# Ant_V1_Sheet.net
KiCad netlist of a schematic drawn in Altium Designer
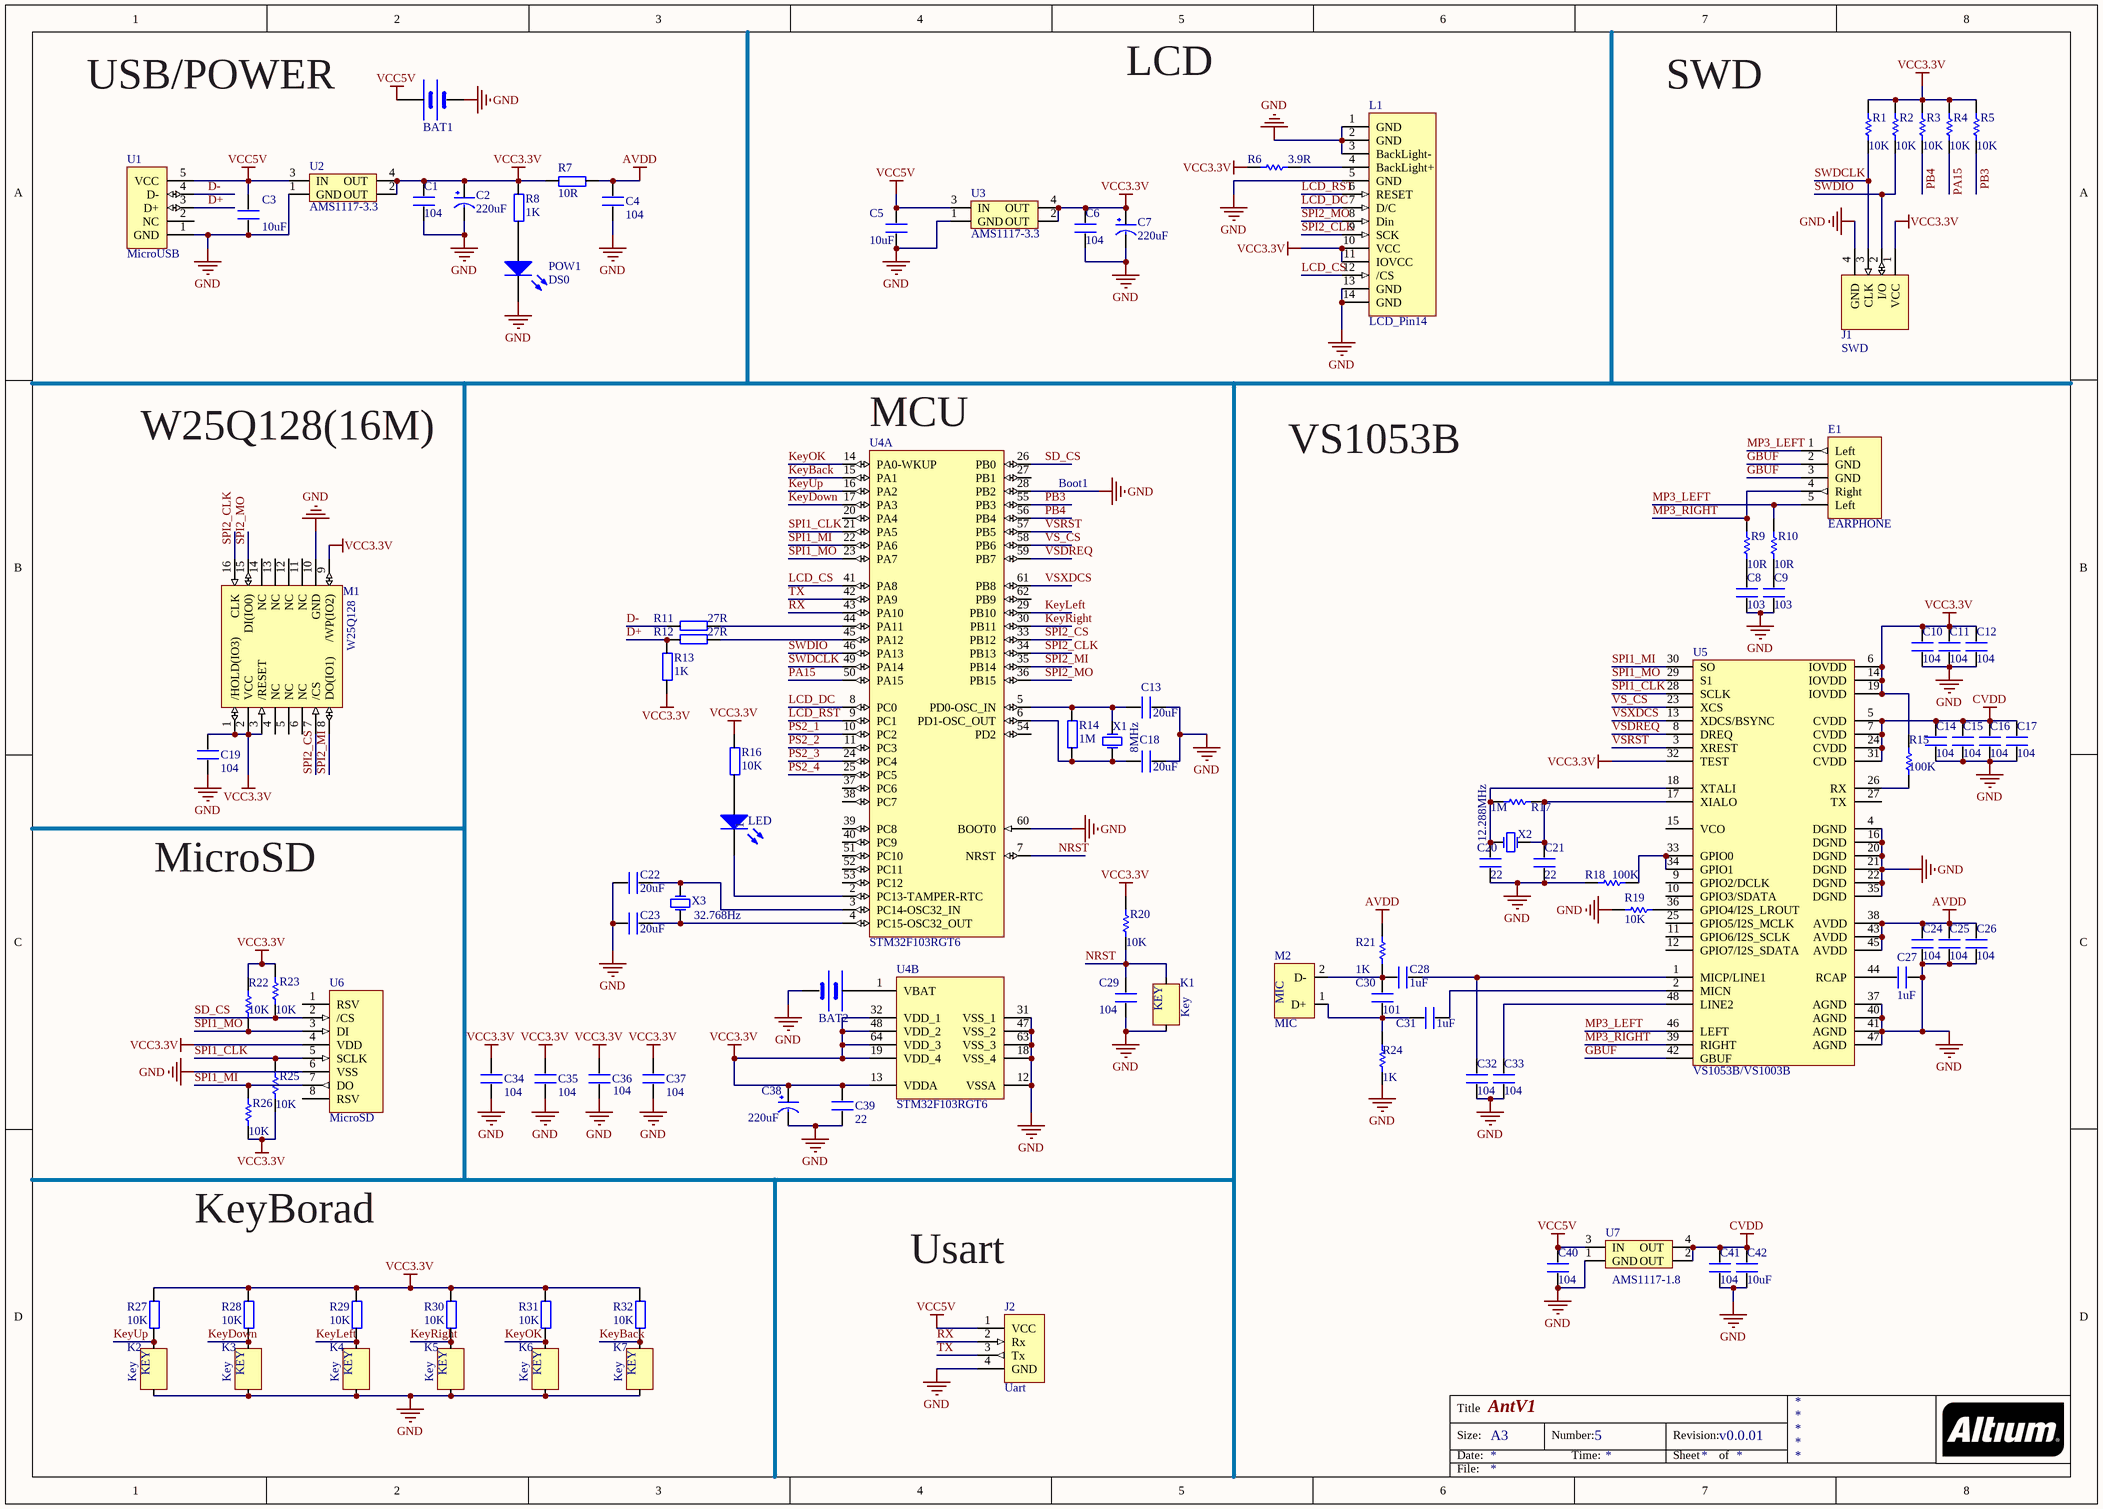
[diagram p0: Ant_V1_Sheet.SchDoc]

(export (version "E")
  (design (tool "Eeschema 10.0.6"))
  (components
    (comp (ref "1")
      (value "LED")
      (footprint "LED_LITTLE")
      (description "Typical RED, GREEN, YELLOW, AMBER GaAs LED")
      (fields (field (name "PUBLISHER") "Altium Limited"))
      (libsource (lib "MP3模块封装库") (part "LED2"))
    )
    (comp (ref "BAT1") (value "BATT") (footprint "BATTERY") (libsource (lib "EliteSTM32封装库") (part "BAT")))
    (comp (ref "BAT2") (value "BATT") (footprint "BATTERY") (libsource (lib "EliteSTM32封装库") (part "BAT")))
    (comp (ref "C1") (value "104") (footprint "0805") (libsource (lib "MP3模块封装库") (part "C")))
    (comp (ref "C2") (value "220uF") (footprint "0805") (libsource (lib "MP3模块封装库") (part "CAP")))
    (comp (ref "C3") (value "10uF") (footprint "0805") (libsource (lib "EliteSTM32封装库") (part "C_2")))
    (comp (ref "C4") (value "104") (footprint "0805") (libsource (lib "MP3模块封装库") (part "C")))
    (comp (ref "C5") (value "10uF") (footprint "0805") (libsource (lib "EliteSTM32封装库") (part "C_2")))
    (comp (ref "C6") (value "104") (footprint "0805") (libsource (lib "MP3模块封装库") (part "C")))
    (comp (ref "C7") (value "220uF") (footprint "0805") (libsource (lib "MP3模块封装库") (part "CAP")))
    (comp (ref "C8") (value "103") (footprint "0805") (libsource (lib "MP3模块封装库") (part "C")))
    (comp (ref "C9") (value "103") (footprint "0805") (libsource (lib "MP3模块封装库") (part "C")))
    (comp (ref "C10") (value "104") (footprint "0805") (libsource (lib "MP3模块封装库") (part "C")))
    (comp (ref "C11") (value "104") (footprint "0805") (libsource (lib "MP3模块封装库") (part "C")))
    (comp (ref "C12") (value "104") (footprint "0805") (libsource (lib "MP3模块封装库") (part "C")))
    (comp (ref "C13") (value "20uF") (footprint "0805") (libsource (lib "EliteSTM32封装库") (part "C_2")))
    (comp (ref "C14") (value "104") (footprint "0805") (libsource (lib "MP3模块封装库") (part "C")))
    (comp (ref "C15") (value "104") (footprint "0805") (libsource (lib "MP3模块封装库") (part "C")))
    (comp (ref "C16") (value "104") (footprint "0805") (libsource (lib "MP3模块封装库") (part "C")))
    (comp (ref "C17") (value "104") (footprint "0805") (libsource (lib "MP3模块封装库") (part "C")))
    (comp (ref "C18") (value "20uF") (footprint "0805") (libsource (lib "EliteSTM32封装库") (part "C_2")))
    (comp (ref "C19") (value "104") (footprint "0805") (libsource (lib "EliteSTM32封装库") (part "C_2")))
    (comp (ref "C20") (value "22") (footprint "0805") (libsource (lib "MP3模块封装库") (part "C")))
    (comp (ref "C21") (value "22") (footprint "0805") (libsource (lib "MP3模块封装库") (part "C")))
    (comp (ref "C22") (value "20uF") (footprint "0805") (libsource (lib "EliteSTM32封装库") (part "C_2")))
    (comp (ref "C23") (value "20uF") (footprint "0805") (libsource (lib "EliteSTM32封装库") (part "C_2")))
    (comp (ref "C24") (value "104") (footprint "0805") (libsource (lib "MP3模块封装库") (part "C")))
    (comp (ref "C25") (value "104") (footprint "0805") (libsource (lib "MP3模块封装库") (part "C")))
    (comp (ref "C26") (value "104") (footprint "0805") (libsource (lib "MP3模块封装库") (part "C")))
    (comp (ref "C27") (value "1uF") (footprint "0805") (libsource (lib "MP3模块封装库") (part "C")))
    (comp (ref "C28") (value "1uF") (footprint "0805") (libsource (lib "MP3模块封装库") (part "C")))
    (comp (ref "C29") (value "104") (footprint "0805") (libsource (lib "EliteSTM32封装库") (part "C")))
    (comp (ref "C30") (value "101") (footprint "0805") (libsource (lib "MP3模块封装库") (part "C")))
    (comp (ref "C31") (value "1uF") (footprint "0805") (libsource (lib "MP3模块封装库") (part "C")))
    (comp (ref "C32") (value "104") (footprint "0805") (libsource (lib "MP3模块封装库") (part "C")))
    (comp (ref "C33") (value "104") (footprint "0805") (libsource (lib "MP3模块封装库") (part "C")))
    (comp (ref "C34") (value "104") (footprint "0805") (libsource (lib "EliteSTM32封装库") (part "C_2")))
    (comp (ref "C35") (value "104") (footprint "0805") (libsource (lib "EliteSTM32封装库") (part "C_2")))
    (comp (ref "C36") (value "104") (footprint "0805") (libsource (lib "EliteSTM32封装库") (part "C_2")))
    (comp (ref "C37") (value "104") (footprint "0805") (libsource (lib "EliteSTM32封装库") (part "C_2")))
    (comp (ref "C38") (value "220uF") (footprint "0805") (libsource (lib "MP3模块封装库") (part "CAP")))
    (comp (ref "C39") (value "22") (footprint "0805") (libsource (lib "MP3模块封装库") (part "C")))
    (comp (ref "C40") (value "104") (footprint "0805") (libsource (lib "MP3模块封装库") (part "C")))
    (comp (ref "C41") (value "104") (footprint "0805") (libsource (lib "MP3模块封装库") (part "C")))
    (comp (ref "C42") (value "10uF") (footprint "0805") (libsource (lib "MP3模块封装库") (part "C")))
    (comp (ref "E1")
      (value "EARPHONE")
      (footprint "EARPHONE")
      (libsource (lib "Ant_V1_Schlib") (part "EARPHONE"))
    )
    (comp (ref "J1") (value "SWD") (footprint "SWD") (libsource (lib "Ant_V1_Schlib") (part "SWD")))
    (comp (ref "J2") (value "Uart") (footprint "Uart") (libsource (lib "Ant_V1_Schlib") (part "Uart")))
    (comp (ref "K1") (value "Key") (footprint "KEY") (libsource (lib "Ant_V1_Schlib") (part "Key")))
    (comp (ref "K2") (value "Key") (footprint "KEY") (libsource (lib "Ant_V1_Schlib") (part "Key")))
    (comp (ref "K3") (value "Key") (footprint "KEY") (libsource (lib "Ant_V1_Schlib") (part "Key")))
    (comp (ref "K4") (value "Key") (footprint "KEY") (libsource (lib "Ant_V1_Schlib") (part "Key")))
    (comp (ref "K5") (value "Key") (footprint "KEY") (libsource (lib "Ant_V1_Schlib") (part "Key")))
    (comp (ref "K6") (value "Key") (footprint "KEY") (libsource (lib "Ant_V1_Schlib") (part "Key")))
    (comp (ref "K7") (value "Key") (footprint "KEY") (libsource (lib "Ant_V1_Schlib") (part "Key")))
    (comp (ref "L1")
      (value "LCD_Pin14")
      (footprint "LCD_PIN14_Rctify")
      (libsource (lib "Ant_V1_Schlib") (part "LCD_Pin14"))
    )
    (comp (ref "M1")
      (value "W25Q128")
      (footprint "W25Q128")
      (libsource (lib "Ant_V1_Schlib") (part "W25Q128"))
    )
    (comp (ref "M2") (value "MIC") (footprint "MIC") (libsource (lib "Ant_V1_Schlib") (part "MIC")))
    (comp (ref "POW1")
      (value "DS0")
      (footprint "LED_LITTLE")
      (description "Typical RED, GREEN, YELLOW, AMBER GaAs LED")
      (fields (field (name "PUBLISHER") "Altium Limited"))
      (libsource (lib "MP3模块封装库") (part "LED2"))
    )
    (comp (ref "R1")
      (value "10K")
      (footprint "0805")
      (description "Resistor")
      (fields (field (name "PUBLISHER") "Altium Limited"))
      (libsource (lib "Miscellaneous Devices") (part "Res1"))
    )
    (comp (ref "R2")
      (value "10K")
      (footprint "0805")
      (description "Resistor")
      (fields (field (name "PUBLISHER") "Altium Limited"))
      (libsource (lib "Miscellaneous Devices") (part "Res1"))
    )
    (comp (ref "R3")
      (value "10K")
      (footprint "0805")
      (description "Resistor")
      (fields (field (name "PUBLISHER") "Altium Limited"))
      (libsource (lib "Miscellaneous Devices") (part "Res1"))
    )
    (comp (ref "R4")
      (value "10K")
      (footprint "0805")
      (description "Resistor")
      (fields (field (name "PUBLISHER") "Altium Limited"))
      (libsource (lib "Miscellaneous Devices") (part "Res1"))
    )
    (comp (ref "R5")
      (value "10K")
      (footprint "0805")
      (description "Resistor")
      (fields (field (name "PUBLISHER") "Altium Limited"))
      (libsource (lib "Miscellaneous Devices") (part "Res1"))
    )
    (comp (ref "R6")
      (value "3.9R")
      (footprint "0805")
      (description "Resistor")
      (fields (field (name "PUBLISHER") "Altium Limited"))
      (libsource (lib "Miscellaneous Devices") (part "Res1"))
    )
    (comp (ref "R7") (value "10R") (footprint "0805") (libsource (lib "MP3模块封装库") (part "R")))
    (comp (ref "R8") (value "1K") (footprint "0805") (libsource (lib "MP3模块封装库") (part "R")))
    (comp (ref "R9")
      (value "10R")
      (footprint "0805")
      (description "Resistor")
      (fields (field (name "PUBLISHER") "Altium Limited"))
      (libsource (lib "Miscellaneous Devices") (part "Res1"))
    )
    (comp (ref "R10")
      (value "10R")
      (footprint "0805")
      (description "Resistor")
      (fields (field (name "PUBLISHER") "Altium Limited"))
      (libsource (lib "Miscellaneous Devices") (part "Res1"))
    )
    (comp (ref "R11") (value "27R") (footprint "0805") (libsource (lib "EliteSTM32封装库") (part "R")))
    (comp (ref "R12") (value "27R") (footprint "0805") (libsource (lib "EliteSTM32封装库") (part "R")))
    (comp (ref "R13") (value "1K") (footprint "0805") (libsource (lib "EliteSTM32封装库") (part "R")))
    (comp (ref "R14") (value "1M") (footprint "0805") (libsource (lib "EliteSTM32封装库") (part "R")))
    (comp (ref "R15")
      (value "100K")
      (footprint "0805")
      (description "Resistor")
      (fields (field (name "PUBLISHER") "Altium Limited"))
      (libsource (lib "Miscellaneous Devices") (part "Res1"))
    )
    (comp (ref "R16") (value "10K") (footprint "0805") (libsource (lib "EliteSTM32封装库") (part "R")))
    (comp (ref "R17")
      (value "1M")
      (footprint "0805")
      (description "Resistor")
      (fields (field (name "PUBLISHER") "Altium Limited"))
      (libsource (lib "Miscellaneous Devices") (part "Res1"))
    )
    (comp (ref "R18")
      (value "100K")
      (footprint "0805")
      (description "Resistor")
      (fields (field (name "PUBLISHER") "Altium Limited"))
      (libsource (lib "Miscellaneous Devices") (part "Res1"))
    )
    (comp (ref "R19")
      (value "10K")
      (footprint "0805")
      (description "Resistor")
      (fields (field (name "PUBLISHER") "Altium Limited"))
      (libsource (lib "Miscellaneous Devices") (part "Res1"))
    )
    (comp (ref "R20")
      (value "10K")
      (footprint "0805")
      (description "Resistor")
      (fields (field (name "PUBLISHER") "Altium Limited"))
      (libsource (lib "Miscellaneous Devices") (part "Res1"))
    )
    (comp (ref "R21")
      (value "1K")
      (footprint "0805")
      (description "Resistor")
      (fields (field (name "PUBLISHER") "Altium Limited"))
      (libsource (lib "Miscellaneous Devices") (part "Res1"))
    )
    (comp (ref "R22")
      (value "10K")
      (footprint "0805")
      (description "Resistor")
      (fields (field (name "PUBLISHER") "Altium Limited"))
      (libsource (lib "Miscellaneous Devices") (part "Res1"))
    )
    (comp (ref "R23")
      (value "10K")
      (footprint "0805")
      (description "Resistor")
      (fields (field (name "PUBLISHER") "Altium Limited"))
      (libsource (lib "Miscellaneous Devices") (part "Res1"))
    )
    (comp (ref "R24")
      (value "1K")
      (footprint "0805")
      (description "Resistor")
      (fields (field (name "PUBLISHER") "Altium Limited"))
      (libsource (lib "Miscellaneous Devices") (part "Res1"))
    )
    (comp (ref "R25")
      (value "10K")
      (footprint "0805")
      (description "Resistor")
      (fields (field (name "PUBLISHER") "Altium Limited"))
      (libsource (lib "Miscellaneous Devices") (part "Res1"))
    )
    (comp (ref "R26")
      (value "10K")
      (footprint "0805")
      (description "Resistor")
      (fields (field (name "PUBLISHER") "Altium Limited"))
      (libsource (lib "Miscellaneous Devices") (part "Res1"))
    )
    (comp (ref "R27") (value "10K") (footprint "0805") (libsource (lib "EliteSTM32封装库") (part "R")))
    (comp (ref "R28") (value "10K") (footprint "0805") (libsource (lib "EliteSTM32封装库") (part "R")))
    (comp (ref "R29") (value "10K") (footprint "0805") (libsource (lib "EliteSTM32封装库") (part "R")))
    (comp (ref "R30") (value "10K") (footprint "0805") (libsource (lib "EliteSTM32封装库") (part "R")))
    (comp (ref "R31") (value "10K") (footprint "0805") (libsource (lib "EliteSTM32封装库") (part "R")))
    (comp (ref "R32") (value "10K") (footprint "0805") (libsource (lib "EliteSTM32封装库") (part "R")))
    (comp (ref "U1") (value "MicroUSB") (footprint "USB") (libsource (lib "Ant_V1_Schlib") (part "MicroUSB")))
    (comp (ref "U2")
      (value "AMS1117-3.3")
      (footprint "AMS1117")
      (libsource (lib "MP3模块封装库") (part "AMS1117"))
    )
    (comp (ref "U3")
      (value "AMS1117-3.3")
      (footprint "AMS1117")
      (libsource (lib "MP3模块封装库") (part "AMS1117"))
    )
    (comp (ref "U4")
      (value "STM32F103RGT6")
      (footprint "STM-LQFP64_N")
      (libsource (lib "STMicroelectronics STM32 F1") (part "STM32F103RGT6"))
    )
    (comp (ref "U5")
      (value "VS1053B/VS1003B")
      (footprint "mTQFP48")
      (libsource (lib "MP3模块封装库") (part "VS1053"))
    )
    (comp (ref "U6")
      (value "MicroSD")
      (footprint "MICROSD")
      (libsource (lib "Ant_V1_Schlib") (part "MicroSD"))
    )
    (comp (ref "U7")
      (value "AMS1117-1.8")
      (footprint "AMS1117")
      (libsource (lib "MP3模块封装库") (part "AMS1117"))
    )
    (comp (ref "X1")
      (value "8MHz")
      (footprint "XTAL_8M")
      (description "Crystal Oscillator")
      (fields (field (name "PUBLISHER") "Altium Limited"))
      (libsource (lib "MP3模块封装库") (part "XTAL"))
    )
    (comp (ref "X2")
      (value "12.288MHz")
      (footprint "XTAL_12.288M")
      (description "Crystal Oscillator")
      (fields (field (name "PUBLISHER") "Altium Limited"))
      (libsource (lib "MP3模块封装库") (part "XTAL"))
    )
    (comp (ref "X3")
      (value "32.768Hz")
      (footprint "XTAL32.768K_4Pin'")
      (description "Crystal Oscillator")
      (fields (field (name "PUBLISHER") "Altium Limited"))
      (libsource (lib "MP3模块封装库") (part "XTAL"))
    )
  )
  (nets
    (net (code "1") (name "/D+") (class "Default")
      (node (ref "R12") (pin "2") (pintype "passive"))
      (node (ref "R13") (pin "2") (pintype "passive"))
      (node (ref "U1") (pin "3") (pinfunction "D+_3") (pintype "bidirectional"))
    )
    (net (code "2") (name "/D-") (class "Default")
      (node (ref "R11") (pin "2") (pintype "passive"))
      (node (ref "U1") (pin "4") (pinfunction "D-_4") (pintype "bidirectional"))
    )
    (net (code "3") (name "/GBUF") (class "Default")
      (node (ref "E1") (pin "2") (pinfunction "GND_2") (pintype "power_in"))
      (node (ref "E1") (pin "3") (pinfunction "GND_3") (pintype "power_in"))
      (node (ref "U5") (pin "42") (pinfunction "GBUF_42") (pintype "passive"))
    )
    (net (code "4") (name "/KeyBack") (class "Default")
      (node (ref "K7") (pin "1") (pinfunction "GND_1") (pintype "power_in"))
      (node (ref "R32") (pin "1") (pintype "passive"))
      (node (ref "U4") (pin "15") (pinfunction "PA1_15") (pintype "bidirectional"))
    )
    (net (code "5") (name "/KeyDown") (class "Default")
      (node (ref "K3") (pin "1") (pinfunction "GND_1") (pintype "power_in"))
      (node (ref "R28") (pin "1") (pintype "passive"))
      (node (ref "U4") (pin "17") (pinfunction "PA3_17") (pintype "bidirectional"))
    )
    (net (code "6") (name "/KeyLeft") (class "Default")
      (node (ref "K4") (pin "1") (pinfunction "GND_1") (pintype "power_in"))
      (node (ref "R29") (pin "1") (pintype "passive"))
      (node (ref "U4") (pin "29") (pinfunction "PB10_29") (pintype "bidirectional"))
    )
    (net (code "7") (name "/KeyOK") (class "Default")
      (node (ref "K6") (pin "1") (pinfunction "GND_1") (pintype "power_in"))
      (node (ref "R31") (pin "1") (pintype "passive"))
      (node (ref "U4") (pin "14") (pinfunction "PA0-WKUP_14") (pintype "bidirectional"))
    )
    (net (code "8") (name "/KeyRight") (class "Default")
      (node (ref "K5") (pin "1") (pinfunction "GND_1") (pintype "power_in"))
      (node (ref "R30") (pin "1") (pintype "passive"))
      (node (ref "U4") (pin "30") (pinfunction "PB11_30") (pintype "bidirectional"))
    )
    (net (code "9") (name "/KeyUp") (class "Default")
      (node (ref "K2") (pin "1") (pinfunction "GND_1") (pintype "power_in"))
      (node (ref "R27") (pin "1") (pintype "passive"))
      (node (ref "U4") (pin "16") (pinfunction "PA2_16") (pintype "bidirectional"))
    )
    (net (code "10") (name "/LCD_CS") (class "Default")
      (node (ref "L1") (pin "12") (pinfunction "/CS_12") (pintype "input"))
      (node (ref "U4") (pin "41") (pinfunction "PA8_41") (pintype "bidirectional"))
    )
    (net (code "11") (name "/LCD_DC") (class "Default")
      (node (ref "L1") (pin "7") (pinfunction "D/C_7") (pintype "input"))
      (node (ref "U4") (pin "8") (pinfunction "PC0_8") (pintype "bidirectional"))
    )
    (net (code "12") (name "/LCD_RST") (class "Default")
      (node (ref "L1") (pin "6") (pinfunction "RESET_6") (pintype "input"))
      (node (ref "U4") (pin "9") (pinfunction "PC1_9") (pintype "bidirectional"))
    )
    (net (code "13") (name "/MP3_LEFT") (class "Default")
      (node (ref "E1") (pin "1") (pinfunction "Left_1") (pintype "output"))
      (node (ref "E1") (pin "5") (pinfunction "Left_5") (pintype "tri_state"))
      (node (ref "R10") (pin "2") (pinfunction "2_2") (pintype "passive"))
      (node (ref "U5") (pin "46") (pinfunction "LEFT_46") (pintype "passive"))
    )
    (net (code "14") (name "/MP3_RIGHT") (class "Default")
      (node (ref "E1") (pin "4") (pinfunction "Right_4") (pintype "output"))
      (node (ref "R9") (pin "2") (pinfunction "2_2") (pintype "passive"))
      (node (ref "U5") (pin "39") (pinfunction "RIGHT_39") (pintype "passive"))
    )
    (net (code "15") (name "/NRST") (class "Default")
      (node (ref "C29") (pin "2") (pintype "passive"))
      (node (ref "K1") (pin "1") (pinfunction "GND_1") (pintype "power_in"))
      (node (ref "R20") (pin "1") (pinfunction "1_1") (pintype "passive"))
      (node (ref "U4") (pin "7") (pinfunction "NRST_7") (pintype "bidirectional"))
    )
    (net (code "16") (name "/PA15") (class "Default")
      (node (ref "R4") (pin "1") (pinfunction "1_1") (pintype "passive"))
      (node (ref "U4") (pin "50") (pinfunction "PA15_50") (pintype "bidirectional"))
    )
    (net (code "17") (name "/PB3") (class "Default")
      (node (ref "R5") (pin "1") (pinfunction "1_1") (pintype "passive"))
      (node (ref "U4") (pin "55") (pinfunction "PB3_55") (pintype "bidirectional"))
    )
    (net (code "18") (name "/PB4") (class "Default")
      (node (ref "R3") (pin "1") (pinfunction "1_1") (pintype "passive"))
      (node (ref "U4") (pin "56") (pinfunction "PB4_56") (pintype "bidirectional"))
    )
    (net (code "19") (name "/PS2_1") (class "Default")
      (node (ref "U4") (pin "10") (pinfunction "PC2_10") (pintype "bidirectional"))
    )
    (net (code "20") (name "/PS2_2") (class "Default")
      (node (ref "U4") (pin "11") (pinfunction "PC3_11") (pintype "bidirectional"))
    )
    (net (code "21") (name "/PS2_3") (class "Default")
      (node (ref "U4") (pin "24") (pinfunction "PC4_24") (pintype "bidirectional"))
    )
    (net (code "22") (name "/PS2_4") (class "Default")
      (node (ref "U4") (pin "25") (pinfunction "PC5_25") (pintype "bidirectional"))
    )
    (net (code "23") (name "/RX") (class "Default")
      (node (ref "J2") (pin "2") (pinfunction "Rx_2") (pintype "input"))
      (node (ref "U4") (pin "43") (pinfunction "PA10_43") (pintype "bidirectional"))
    )
    (net (code "24") (name "/SD_CS") (class "Default")
      (node (ref "R23") (pin "1") (pinfunction "1_1") (pintype "passive"))
      (node (ref "U4") (pin "26") (pinfunction "PB0_26") (pintype "bidirectional"))
      (node (ref "U6") (pin "2") (pinfunction "/CS_2") (pintype "input"))
    )
    (net (code "25") (name "/SPI1_CLK") (class "Default")
      (node (ref "R25") (pin "2") (pinfunction "2_2") (pintype "passive"))
      (node (ref "U4") (pin "21") (pinfunction "PA5_21") (pintype "bidirectional"))
      (node (ref "U5") (pin "28") (pinfunction "SCLK_28") (pintype "passive"))
      (node (ref "U6") (pin "5") (pinfunction "SCLK_5") (pintype "input"))
    )
    (net (code "26") (name "/SPI1_MI") (class "Default")
      (node (ref "R26") (pin "2") (pinfunction "2_2") (pintype "passive"))
      (node (ref "U4") (pin "22") (pinfunction "PA6_22") (pintype "bidirectional"))
      (node (ref "U5") (pin "30") (pinfunction "SO_30") (pintype "passive"))
      (node (ref "U6") (pin "7") (pinfunction "DO_7") (pintype "output"))
    )
    (net (code "27") (name "/SPI1_MO") (class "Default")
      (node (ref "R22") (pin "1") (pinfunction "1_1") (pintype "passive"))
      (node (ref "U4") (pin "23") (pinfunction "PA7_23") (pintype "bidirectional"))
      (node (ref "U5") (pin "29") (pinfunction "S1_29") (pintype "passive"))
      (node (ref "U6") (pin "3") (pinfunction "DI_3") (pintype "input"))
    )
    (net (code "28") (name "/SPI2_CLK") (class "Default")
      (node (ref "L1") (pin "9") (pinfunction "SCK_9") (pintype "input"))
      (node (ref "M1") (pin "16") (pinfunction "CLK_16") (pintype "input"))
      (node (ref "U4") (pin "34") (pinfunction "PB13_34") (pintype "bidirectional"))
    )
    (net (code "29") (name "/SPI2_CS") (class "Default")
      (node (ref "M1") (pin "7") (pinfunction "/CS_7") (pintype "input"))
      (node (ref "U4") (pin "33") (pinfunction "PB12_33") (pintype "bidirectional"))
    )
    (net (code "30") (name "/SPI2_MI") (class "Default")
      (node (ref "M1") (pin "8") (pinfunction "DO(IO1)_8") (pintype "bidirectional"))
      (node (ref "U4") (pin "35") (pinfunction "PB14_35") (pintype "bidirectional"))
    )
    (net (code "31") (name "/SPI2_MO") (class "Default")
      (node (ref "L1") (pin "8") (pinfunction "Din_8") (pintype "input"))
      (node (ref "M1") (pin "15") (pinfunction "DI(IO0)_15") (pintype "bidirectional"))
      (node (ref "U4") (pin "36") (pinfunction "PB15_36") (pintype "bidirectional"))
    )
    (net (code "32") (name "/SWDCLK") (class "Default")
      (node (ref "J1") (pin "3") (pinfunction "CLK_3") (pintype "input"))
      (node (ref "R1") (pin "1") (pinfunction "1_1") (pintype "passive"))
      (node (ref "U4") (pin "49") (pinfunction "PA14_49") (pintype "bidirectional"))
    )
    (net (code "33") (name "/SWDIO") (class "Default")
      (node (ref "J1") (pin "2") (pinfunction "I/O_2") (pintype "bidirectional"))
      (node (ref "R2") (pin "1") (pinfunction "1_1") (pintype "passive"))
      (node (ref "U4") (pin "46") (pinfunction "PA13_46") (pintype "bidirectional"))
    )
    (net (code "34") (name "/TX") (class "Default")
      (node (ref "J2") (pin "3") (pinfunction "Tx_3") (pintype "output"))
      (node (ref "U4") (pin "42") (pinfunction "PA9_42") (pintype "bidirectional"))
    )
    (net (code "35") (name "/VSDREQ") (class "Default")
      (node (ref "U4") (pin "59") (pinfunction "PB7_59") (pintype "bidirectional"))
      (node (ref "U5") (pin "8") (pinfunction "DREQ_8") (pintype "passive"))
    )
    (net (code "36") (name "/VSRST") (class "Default")
      (node (ref "U4") (pin "57") (pinfunction "PB5_57") (pintype "bidirectional"))
      (node (ref "U5") (pin "3") (pinfunction "XREST_3") (pintype "passive"))
    )
    (net (code "37") (name "/VSXDCS") (class "Default")
      (node (ref "U4") (pin "61") (pinfunction "PB8_61") (pintype "bidirectional"))
      (node (ref "U5") (pin "13") (pinfunction "XDCS/BSYNC_13") (pintype "passive"))
    )
    (net (code "38") (name "/VS_CS") (class "Default")
      (node (ref "U4") (pin "58") (pinfunction "PB6_58") (pintype "bidirectional"))
      (node (ref "U5") (pin "23") (pinfunction "XCS_23") (pintype "passive"))
    )
    (net (code "39") (name "AVDD") (class "Default")
      (node (ref "C24") (pin "1") (pintype "passive"))
      (node (ref "C25") (pin "1") (pintype "passive"))
      (node (ref "C26") (pin "1") (pintype "passive"))
      (node (ref "C4") (pin "2") (pintype "passive"))
      (node (ref "R21") (pin "1") (pinfunction "1_1") (pintype "passive"))
      (node (ref "R7") (pin "2") (pintype "passive"))
      (node (ref "U5") (pin "38") (pinfunction "AVDD_38") (pintype "passive"))
      (node (ref "U5") (pin "43") (pinfunction "AVDD_43") (pintype "passive"))
      (node (ref "U5") (pin "45") (pinfunction "AVDD_45") (pintype "passive"))
    )
    (net (code "40") (name "CVDD") (class "Default")
      (node (ref "C14") (pin "1") (pintype "passive"))
      (node (ref "C15") (pin "1") (pintype "passive"))
      (node (ref "C16") (pin "1") (pintype "passive"))
      (node (ref "C17") (pin "1") (pintype "passive"))
      (node (ref "C41") (pin "2") (pintype "passive"))
      (node (ref "C42") (pin "2") (pintype "passive"))
      (node (ref "U5") (pin "24") (pinfunction "CVDD_24") (pintype "passive"))
      (node (ref "U5") (pin "31") (pinfunction "CVDD_31") (pintype "passive"))
      (node (ref "U5") (pin "5") (pinfunction "CVDD_5") (pintype "passive"))
      (node (ref "U5") (pin "7") (pinfunction "CVDD_7") (pintype "passive"))
      (node (ref "U7") (pin "2") (pinfunction "OUT_2") (pintype "passive"))
      (node (ref "U7") (pin "4") (pinfunction "OUT_4") (pintype "passive"))
    )
    (net (code "41") (name "GND") (class "Default")
      (node (ref "BAT1") (pin "2") (pinfunction "GND_2") (pintype "passive"))
      (node (ref "BAT2") (pin "2") (pinfunction "GND_2") (pintype "passive"))
      (node (ref "C1") (pin "1") (pintype "passive"))
      (node (ref "C10") (pin "2") (pintype "passive"))
      (node (ref "C11") (pin "2") (pintype "passive"))
      (node (ref "C12") (pin "2") (pintype "passive"))
      (node (ref "C13") (pin "2") (pintype "passive"))
      (node (ref "C14") (pin "2") (pintype "passive"))
      (node (ref "C15") (pin "2") (pintype "passive"))
      (node (ref "C16") (pin "2") (pintype "passive"))
      (node (ref "C17") (pin "2") (pintype "passive"))
      (node (ref "C18") (pin "2") (pintype "passive"))
      (node (ref "C19") (pin "2") (pintype "passive"))
      (node (ref "C2") (pin "2") (pinfunction "GND_2") (pintype "passive"))
      (node (ref "C20") (pin "2") (pintype "passive"))
      (node (ref "C21") (pin "2") (pintype "passive"))
      (node (ref "C22") (pin "1") (pintype "passive"))
      (node (ref "C23") (pin "1") (pintype "passive"))
      (node (ref "C24") (pin "2") (pintype "passive"))
      (node (ref "C25") (pin "2") (pintype "passive"))
      (node (ref "C26") (pin "2") (pintype "passive"))
      (node (ref "C27") (pin "2") (pintype "passive"))
      (node (ref "C29") (pin "1") (pintype "passive"))
      (node (ref "C3") (pin "1") (pintype "passive"))
      (node (ref "C32") (pin "1") (pintype "passive"))
      (node (ref "C33") (pin "1") (pintype "passive"))
      (node (ref "C34") (pin "1") (pintype "passive"))
      (node (ref "C35") (pin "1") (pintype "passive"))
      (node (ref "C36") (pin "1") (pintype "passive"))
      (node (ref "C37") (pin "1") (pintype "passive"))
      (node (ref "C38") (pin "2") (pinfunction "GND_2") (pintype "passive"))
      (node (ref "C39") (pin "1") (pintype "passive"))
      (node (ref "C4") (pin "1") (pintype "passive"))
      (node (ref "C40") (pin "1") (pintype "passive"))
      (node (ref "C41") (pin "1") (pintype "passive"))
      (node (ref "C42") (pin "1") (pintype "passive"))
      (node (ref "C5") (pin "1") (pintype "passive"))
      (node (ref "C6") (pin "1") (pintype "passive"))
      (node (ref "C7") (pin "2") (pinfunction "GND_2") (pintype "passive"))
      (node (ref "C8") (pin "2") (pintype "passive"))
      (node (ref "C9") (pin "2") (pintype "passive"))
      (node (ref "J1") (pin "4") (pinfunction "GND_4") (pintype "power_in"))
      (node (ref "J2") (pin "4") (pinfunction "GND_4") (pintype "power_in"))
      (node (ref "K1") (pin "2") (pinfunction "GND_2") (pintype "power_in"))
      (node (ref "K2") (pin "2") (pinfunction "GND_2") (pintype "power_in"))
      (node (ref "K3") (pin "2") (pinfunction "GND_2") (pintype "power_in"))
      (node (ref "K4") (pin "2") (pinfunction "GND_2") (pintype "power_in"))
      (node (ref "K5") (pin "2") (pinfunction "GND_2") (pintype "power_in"))
      (node (ref "K6") (pin "2") (pinfunction "GND_2") (pintype "power_in"))
      (node (ref "K7") (pin "2") (pinfunction "GND_2") (pintype "power_in"))
      (node (ref "L1") (pin "1") (pinfunction "GND_1") (pintype "power_in"))
      (node (ref "L1") (pin "13") (pinfunction "GND_13") (pintype "power_in"))
      (node (ref "L1") (pin "14") (pinfunction "GND_14") (pintype "power_in"))
      (node (ref "L1") (pin "2") (pinfunction "GND_2") (pintype "power_in"))
      (node (ref "L1") (pin "3") (pinfunction "BackLight-_3") (pintype "power_in"))
      (node (ref "L1") (pin "5") (pinfunction "GND_5") (pintype "power_in"))
      (node (ref "M1") (pin "10") (pinfunction "GND_10") (pintype "power_in"))
      (node (ref "POW1") (pin "2") (pinfunction "K_2") (pintype "passive"))
      (node (ref "R18") (pin "2") (pinfunction "2_2") (pintype "passive"))
      (node (ref "R19") (pin "1") (pinfunction "1_1") (pintype "passive"))
      (node (ref "R24") (pin "2") (pinfunction "2_2") (pintype "passive"))
      (node (ref "U1") (pin "1") (pinfunction "GND_1") (pintype "power_in"))
      (node (ref "U2") (pin "1") (pinfunction "GND_1") (pintype "passive"))
      (node (ref "U3") (pin "1") (pinfunction "GND_1") (pintype "passive"))
      (node (ref "U4") (pin "12") (pinfunction "VSSA_12") (pintype "power_in"))
      (node (ref "U4") (pin "18") (pinfunction "VSS_4_18") (pintype "power_in"))
      (node (ref "U4") (pin "28") (pinfunction "PB2_28") (pintype "bidirectional"))
      (node (ref "U4") (pin "31") (pinfunction "VSS_1_31") (pintype "power_in"))
      (node (ref "U4") (pin "47") (pinfunction "VSS_2_47") (pintype "power_in"))
      (node (ref "U4") (pin "60") (pinfunction "BOOT0_60") (pintype "input"))
      (node (ref "U4") (pin "63") (pinfunction "VSS_3_63") (pintype "power_in"))
      (node (ref "U5") (pin "16") (pinfunction "DGND_16") (pintype "passive"))
      (node (ref "U5") (pin "20") (pinfunction "DGND_20") (pintype "passive"))
      (node (ref "U5") (pin "21") (pinfunction "DGND_21") (pintype "passive"))
      (node (ref "U5") (pin "22") (pinfunction "DGND_22") (pintype "passive"))
      (node (ref "U5") (pin "35") (pinfunction "DGND_35") (pintype "passive"))
      (node (ref "U5") (pin "37") (pinfunction "AGND_37") (pintype "passive"))
      (node (ref "U5") (pin "4") (pinfunction "DGND_4") (pintype "passive"))
      (node (ref "U5") (pin "40") (pinfunction "AGND_40") (pintype "passive"))
      (node (ref "U5") (pin "41") (pinfunction "AGND_41") (pintype "passive"))
      (node (ref "U5") (pin "47") (pinfunction "AGND_47") (pintype "passive"))
      (node (ref "U6") (pin "6") (pinfunction "VSS_6") (pintype "power_in"))
      (node (ref "U7") (pin "1") (pinfunction "GND_1") (pintype "passive"))
    )
    (net (code "42") (name "Net-(1-A)") (class "Default")
      (node (ref "1") (pin "1") (pinfunction "A_1") (pintype "passive"))
      (node (ref "R16") (pin "1") (pintype "passive"))
    )
    (net (code "43") (name "Net-(1-K)") (class "Default")
      (node (ref "1") (pin "2") (pinfunction "K_2") (pintype "passive"))
      (node (ref "U4") (pin "2") (pinfunction "PC13-TAMPER-RTC_2") (pintype "bidirectional"))
    )
    (net (code "44") (name "Net-(BAT2-VCC)") (class "Default")
      (node (ref "BAT2") (pin "1") (pinfunction "VCC_1") (pintype "passive"))
      (node (ref "U4") (pin "1") (pinfunction "VBAT_1") (pintype "power_in"))
    )
    (net (code "45") (name "Net-(C8-Pad1)") (class "Default")
      (node (ref "C8") (pin "1") (pintype "passive"))
      (node (ref "R9") (pin "1") (pinfunction "1_1") (pintype "passive"))
    )
    (net (code "46") (name "Net-(C9-Pad1)") (class "Default")
      (node (ref "C9") (pin "1") (pintype "passive"))
      (node (ref "R10") (pin "1") (pinfunction "1_1") (pintype "passive"))
    )
    (net (code "47") (name "Net-(L1-BackLight+)") (class "Default")
      (node (ref "L1") (pin "4") (pinfunction "BackLight+_4") (pintype "power_in"))
      (node (ref "R6") (pin "1") (pinfunction "1_1") (pintype "passive"))
    )
    (net (code "48") (name "Net-(M2-D+)") (class "Default")
      (node (ref "C30") (pin "1") (pintype "passive"))
      (node (ref "C31") (pin "2") (pintype "passive"))
      (node (ref "M2") (pin "1") (pinfunction "D+_1") (pintype "power_in"))
      (node (ref "R24") (pin "1") (pinfunction "1_1") (pintype "passive"))
    )
    (net (code "49") (name "Net-(M2-D-)") (class "Default")
      (node (ref "C28") (pin "1") (pintype "passive"))
      (node (ref "C30") (pin "2") (pintype "passive"))
      (node (ref "M2") (pin "2") (pinfunction "D-_2") (pintype "power_in"))
      (node (ref "R21") (pin "2") (pinfunction "2_2") (pintype "passive"))
    )
    (net (code "50") (name "Net-(POW1-A)") (class "Default")
      (node (ref "POW1") (pin "1") (pinfunction "A_1") (pintype "passive"))
      (node (ref "R8") (pin "1") (pintype "passive"))
    )
    (net (code "51") (name "Net-(U4A-PA11)") (class "Default")
      (node (ref "R11") (pin "1") (pintype "passive"))
      (node (ref "U4") (pin "44") (pinfunction "PA11_44") (pintype "bidirectional"))
    )
    (net (code "52") (name "Net-(U4A-PA12)") (class "Default")
      (node (ref "R12") (pin "1") (pintype "passive"))
      (node (ref "U4") (pin "45") (pinfunction "PA12_45") (pintype "bidirectional"))
    )
    (net (code "53") (name "Net-(U4A-PC14-OSC32_IN)") (class "Default")
      (node (ref "C22") (pin "2") (pintype "passive"))
      (node (ref "U4") (pin "3") (pinfunction "PC14-OSC32_IN_3") (pintype "bidirectional"))
      (node (ref "X3") (pin "2") (pinfunction "OSC2_2") (pintype "passive"))
    )
    (net (code "54") (name "Net-(U4A-PC15-OSC32_OUT)") (class "Default")
      (node (ref "C23") (pin "2") (pintype "passive"))
      (node (ref "U4") (pin "4") (pinfunction "PC15-OSC32_OUT_4") (pintype "bidirectional"))
      (node (ref "X3") (pin "1") (pinfunction "OSC1_1") (pintype "passive"))
    )
    (net (code "55") (name "Net-(U4A-PD0-OSC_IN)") (class "Default")
      (node (ref "C13") (pin "1") (pintype "passive"))
      (node (ref "R14") (pin "2") (pintype "passive"))
      (node (ref "U4") (pin "5") (pinfunction "PD0-OSC_IN_5") (pintype "bidirectional"))
      (node (ref "X1") (pin "1") (pinfunction "OSC1_1") (pintype "passive"))
    )
    (net (code "56") (name "Net-(U4A-PD1-OSC_OUT)") (class "Default")
      (node (ref "C18") (pin "1") (pintype "passive"))
      (node (ref "R14") (pin "1") (pintype "passive"))
      (node (ref "U4") (pin "6") (pinfunction "PD1-OSC_OUT_6") (pintype "bidirectional"))
      (node (ref "X1") (pin "2") (pinfunction "OSC2_2") (pintype "passive"))
    )
    (net (code "57") (name "Net-(U5-GPIO0)") (class "Default")
      (node (ref "R18") (pin "1") (pinfunction "1_1") (pintype "passive"))
      (node (ref "U5") (pin "33") (pinfunction "GPIO0_33") (pintype "passive"))
      (node (ref "U5") (pin "34") (pinfunction "GPIO1_34") (pintype "passive"))
    )
    (net (code "58") (name "Net-(U5-GPIO4{slash}I2S_LROUT)") (class "Default")
      (node (ref "R19") (pin "2") (pinfunction "2_2") (pintype "passive"))
      (node (ref "U5") (pin "36") (pinfunction "GPIO4/I2S_LROUT_36") (pintype "passive"))
    )
    (net (code "59") (name "Net-(U5-LINE2)") (class "Default")
      (node (ref "C33") (pin "2") (pintype "passive"))
      (node (ref "U5") (pin "48") (pinfunction "LINE2_48") (pintype "passive"))
    )
    (net (code "60") (name "Net-(U5-MICN)") (class "Default")
      (node (ref "C31") (pin "1") (pintype "passive"))
      (node (ref "U5") (pin "2") (pinfunction "MICN_2") (pintype "passive"))
    )
    (net (code "61") (name "Net-(U5-MICP{slash}LINE1)") (class "Default")
      (node (ref "C28") (pin "2") (pintype "passive"))
      (node (ref "C32") (pin "2") (pintype "passive"))
      (node (ref "U5") (pin "1") (pinfunction "MICP/LINE1_1") (pintype "passive"))
    )
    (net (code "62") (name "Net-(U5-RCAP)") (class "Default")
      (node (ref "C27") (pin "1") (pintype "passive"))
      (node (ref "U5") (pin "44") (pinfunction "RCAP_44") (pintype "passive"))
    )
    (net (code "63") (name "Net-(U5-RX)") (class "Default")
      (node (ref "R15") (pin "1") (pinfunction "1_1") (pintype "passive"))
      (node (ref "U5") (pin "26") (pinfunction "RX_26") (pintype "passive"))
    )
    (net (code "64") (name "Net-(U5-XIALO)") (class "Default")
      (node (ref "C21") (pin "1") (pintype "passive"))
      (node (ref "R17") (pin "1") (pinfunction "1_1") (pintype "passive"))
      (node (ref "U5") (pin "17") (pinfunction "XIALO_17") (pintype "passive"))
      (node (ref "X2") (pin "2") (pinfunction "OSC2_2") (pintype "passive"))
    )
    (net (code "65") (name "Net-(U5-XTALI)") (class "Default")
      (node (ref "C20") (pin "1") (pintype "passive"))
      (node (ref "R17") (pin "2") (pinfunction "2_2") (pintype "passive"))
      (node (ref "U5") (pin "18") (pinfunction "XTALI_18") (pintype "passive"))
      (node (ref "X2") (pin "1") (pinfunction "OSC1_1") (pintype "passive"))
    )
    (net (code "66") (name "VCC3.3V") (class "Default")
      (node (ref "C1") (pin "2") (pintype "passive"))
      (node (ref "C10") (pin "1") (pintype "passive"))
      (node (ref "C11") (pin "1") (pintype "passive"))
      (node (ref "C12") (pin "1") (pintype "passive"))
      (node (ref "C19") (pin "1") (pintype "passive"))
      (node (ref "C2") (pin "1") (pinfunction "VCC_1") (pintype "passive"))
      (node (ref "C34") (pin "2") (pintype "passive"))
      (node (ref "C35") (pin "2") (pintype "passive"))
      (node (ref "C36") (pin "2") (pintype "passive"))
      (node (ref "C37") (pin "2") (pintype "passive"))
      (node (ref "C38") (pin "1") (pinfunction "VCC_1") (pintype "passive"))
      (node (ref "C39") (pin "2") (pintype "passive"))
      (node (ref "C6") (pin "2") (pintype "passive"))
      (node (ref "C7") (pin "1") (pinfunction "VCC_1") (pintype "passive"))
      (node (ref "J1") (pin "1") (pinfunction "VCC_1") (pintype "power_in"))
      (node (ref "L1") (pin "10") (pinfunction "VCC_10") (pintype "power_in"))
      (node (ref "L1") (pin "11") (pinfunction "IOVCC_11") (pintype "power_in"))
      (node (ref "M1") (pin "1") (pinfunction "/HOLD(IO3)_1") (pintype "bidirectional"))
      (node (ref "M1") (pin "2") (pinfunction "VCC_2") (pintype "power_in"))
      (node (ref "M1") (pin "3") (pinfunction "/RESET_3") (pintype "input"))
      (node (ref "M1") (pin "9") (pinfunction "/WP(IO2)_9") (pintype "bidirectional"))
      (node (ref "R1") (pin "2") (pinfunction "2_2") (pintype "passive"))
      (node (ref "R13") (pin "1") (pintype "passive"))
      (node (ref "R15") (pin "2") (pinfunction "2_2") (pintype "passive"))
      (node (ref "R16") (pin "2") (pintype "passive"))
      (node (ref "R2") (pin "2") (pinfunction "2_2") (pintype "passive"))
      (node (ref "R20") (pin "2") (pinfunction "2_2") (pintype "passive"))
      (node (ref "R22") (pin "2") (pinfunction "2_2") (pintype "passive"))
      (node (ref "R23") (pin "2") (pinfunction "2_2") (pintype "passive"))
      (node (ref "R25") (pin "1") (pinfunction "1_1") (pintype "passive"))
      (node (ref "R26") (pin "1") (pinfunction "1_1") (pintype "passive"))
      (node (ref "R27") (pin "2") (pintype "passive"))
      (node (ref "R28") (pin "2") (pintype "passive"))
      (node (ref "R29") (pin "2") (pintype "passive"))
      (node (ref "R3") (pin "2") (pinfunction "2_2") (pintype "passive"))
      (node (ref "R30") (pin "2") (pintype "passive"))
      (node (ref "R31") (pin "2") (pintype "passive"))
      (node (ref "R32") (pin "2") (pintype "passive"))
      (node (ref "R4") (pin "2") (pinfunction "2_2") (pintype "passive"))
      (node (ref "R5") (pin "2") (pinfunction "2_2") (pintype "passive"))
      (node (ref "R6") (pin "2") (pinfunction "2_2") (pintype "passive"))
      (node (ref "R7") (pin "1") (pintype "passive"))
      (node (ref "R8") (pin "2") (pintype "passive"))
      (node (ref "U2") (pin "2") (pinfunction "OUT_2") (pintype "passive"))
      (node (ref "U2") (pin "4") (pinfunction "OUT_4") (pintype "passive"))
      (node (ref "U3") (pin "2") (pinfunction "OUT_2") (pintype "passive"))
      (node (ref "U3") (pin "4") (pinfunction "OUT_4") (pintype "passive"))
      (node (ref "U4") (pin "13") (pinfunction "VDDA_13") (pintype "power_in"))
      (node (ref "U4") (pin "19") (pinfunction "VDD_4_19") (pintype "power_in"))
      (node (ref "U4") (pin "32") (pinfunction "VDD_1_32") (pintype "power_in"))
      (node (ref "U4") (pin "48") (pinfunction "VDD_2_48") (pintype "power_in"))
      (node (ref "U4") (pin "64") (pinfunction "VDD_3_64") (pintype "power_in"))
      (node (ref "U5") (pin "14") (pinfunction "IOVDD_14") (pintype "passive"))
      (node (ref "U5") (pin "19") (pinfunction "IOVDD_19") (pintype "passive"))
      (node (ref "U5") (pin "32") (pinfunction "TEST_32") (pintype "passive"))
      (node (ref "U5") (pin "6") (pinfunction "IOVDD_6") (pintype "passive"))
      (node (ref "U6") (pin "4") (pinfunction "VDD_4") (pintype "power_in"))
    )
    (net (code "67") (name "VCC5V") (class "Default")
      (node (ref "BAT1") (pin "1") (pinfunction "VCC_1") (pintype "passive"))
      (node (ref "C3") (pin "2") (pintype "passive"))
      (node (ref "C40") (pin "2") (pintype "passive"))
      (node (ref "C5") (pin "2") (pintype "passive"))
      (node (ref "J2") (pin "1") (pinfunction "VCC_1") (pintype "power_in"))
      (node (ref "U1") (pin "5") (pinfunction "VCC_5") (pintype "power_in"))
      (node (ref "U2") (pin "3") (pinfunction "IN_3") (pintype "passive"))
      (node (ref "U3") (pin "3") (pinfunction "IN_3") (pintype "passive"))
      (node (ref "U7") (pin "3") (pinfunction "IN_3") (pintype "passive"))
    )
    (net (code "68") (name "unconnected-(M1-NC-Pad4)") (class "Default")
      (node (ref "M1") (pin "4") (pinfunction "NC_4") (pintype "tri_state"))
    )
    (net (code "69") (name "unconnected-(M1-NC-Pad5)") (class "Default")
      (node (ref "M1") (pin "5") (pinfunction "NC_5") (pintype "tri_state"))
    )
    (net (code "70") (name "unconnected-(M1-NC-Pad6)") (class "Default")
      (node (ref "M1") (pin "6") (pinfunction "NC_6") (pintype "tri_state"))
    )
    (net (code "71") (name "unconnected-(M1-NC-Pad11)") (class "Default")
      (node (ref "M1") (pin "11") (pinfunction "NC_11") (pintype "tri_state"))
    )
    (net (code "72") (name "unconnected-(M1-NC-Pad12)") (class "Default")
      (node (ref "M1") (pin "12") (pinfunction "NC_12") (pintype "tri_state"))
    )
    (net (code "73") (name "unconnected-(M1-NC-Pad13)") (class "Default")
      (node (ref "M1") (pin "13") (pinfunction "NC_13") (pintype "tri_state"))
    )
    (net (code "74") (name "unconnected-(M1-NC-Pad14)") (class "Default")
      (node (ref "M1") (pin "14") (pinfunction "NC_14") (pintype "tri_state"))
    )
    (net (code "75") (name "unconnected-(U1-NC-Pad2)") (class "Default")
      (node (ref "U1") (pin "2") (pinfunction "NC_2") (pintype "tri_state"))
    )
    (net (code "76") (name "unconnected-(U4A-PA4-Pad20)") (class "Default")
      (node (ref "U4") (pin "20") (pinfunction "PA4_20") (pintype "bidirectional"))
    )
    (net (code "77") (name "unconnected-(U4A-PB1-Pad27)") (class "Default")
      (node (ref "U4") (pin "27") (pinfunction "PB1_27") (pintype "bidirectional"))
    )
    (net (code "78") (name "unconnected-(U4A-PB9-Pad62)") (class "Default")
      (node (ref "U4") (pin "62") (pinfunction "PB9_62") (pintype "bidirectional"))
    )
    (net (code "79") (name "unconnected-(U4A-PC6-Pad37)") (class "Default")
      (node (ref "U4") (pin "37") (pinfunction "PC6_37") (pintype "bidirectional"))
    )
    (net (code "80") (name "unconnected-(U4A-PC7-Pad38)") (class "Default")
      (node (ref "U4") (pin "38") (pinfunction "PC7_38") (pintype "bidirectional"))
    )
    (net (code "81") (name "unconnected-(U4A-PC8-Pad39)") (class "Default")
      (node (ref "U4") (pin "39") (pinfunction "PC8_39") (pintype "bidirectional"))
    )
    (net (code "82") (name "unconnected-(U4A-PC9-Pad40)") (class "Default")
      (node (ref "U4") (pin "40") (pinfunction "PC9_40") (pintype "bidirectional"))
    )
    (net (code "83") (name "unconnected-(U4A-PC10-Pad51)") (class "Default")
      (node (ref "U4") (pin "51") (pinfunction "PC10_51") (pintype "bidirectional"))
    )
    (net (code "84") (name "unconnected-(U4A-PC11-Pad52)") (class "Default")
      (node (ref "U4") (pin "52") (pinfunction "PC11_52") (pintype "bidirectional"))
    )
    (net (code "85") (name "unconnected-(U4A-PC12-Pad53)") (class "Default")
      (node (ref "U4") (pin "53") (pinfunction "PC12_53") (pintype "bidirectional"))
    )
    (net (code "86") (name "unconnected-(U4A-PD2-Pad54)") (class "Default")
      (node (ref "U4") (pin "54") (pinfunction "PD2_54") (pintype "bidirectional"))
    )
    (net (code "87") (name "unconnected-(U5-GPIO2{slash}DCLK-Pad9)") (class "Default")
      (node (ref "U5") (pin "9") (pinfunction "GPIO2/DCLK_9") (pintype "passive"))
    )
    (net (code "88") (name "unconnected-(U5-GPIO3{slash}SDATA-Pad10)") (class "Default")
      (node (ref "U5") (pin "10") (pinfunction "GPIO3/SDATA_10") (pintype "passive"))
    )
    (net (code "89") (name "unconnected-(U5-GPIO5{slash}I2S_MCLK-Pad25)") (class "Default")
      (node (ref "U5") (pin "25") (pinfunction "GPIO5/I2S_MCLK_25") (pintype "passive"))
    )
    (net (code "90") (name "unconnected-(U5-GPIO6{slash}I2S_SCLK-Pad11)") (class "Default")
      (node (ref "U5") (pin "11") (pinfunction "GPIO6/I2S_SCLK_11") (pintype "passive"))
    )
    (net (code "91") (name "unconnected-(U5-GPIO7{slash}I2S_SDATA-Pad12)") (class "Default")
      (node (ref "U5") (pin "12") (pinfunction "GPIO7/I2S_SDATA_12") (pintype "passive"))
    )
    (net (code "92") (name "unconnected-(U5-TX-Pad27)") (class "Default")
      (node (ref "U5") (pin "27") (pinfunction "TX_27") (pintype "passive"))
    )
    (net (code "93") (name "unconnected-(U5-VCO-Pad15)") (class "Default")
      (node (ref "U5") (pin "15") (pinfunction "VCO_15") (pintype "passive"))
    )
    (net (code "94") (name "unconnected-(U6-RSV-Pad1)") (class "Default")
      (node (ref "U6") (pin "1") (pinfunction "RSV_1") (pintype "tri_state"))
    )
    (net (code "95") (name "unconnected-(U6-RSV-Pad8)") (class "Default")
      (node (ref "U6") (pin "8") (pinfunction "RSV_8") (pintype "tri_state"))
    )
  )
)
